# ADC-Peripherals.net
KiCad netlist of a schematic drawn in Altium Designer
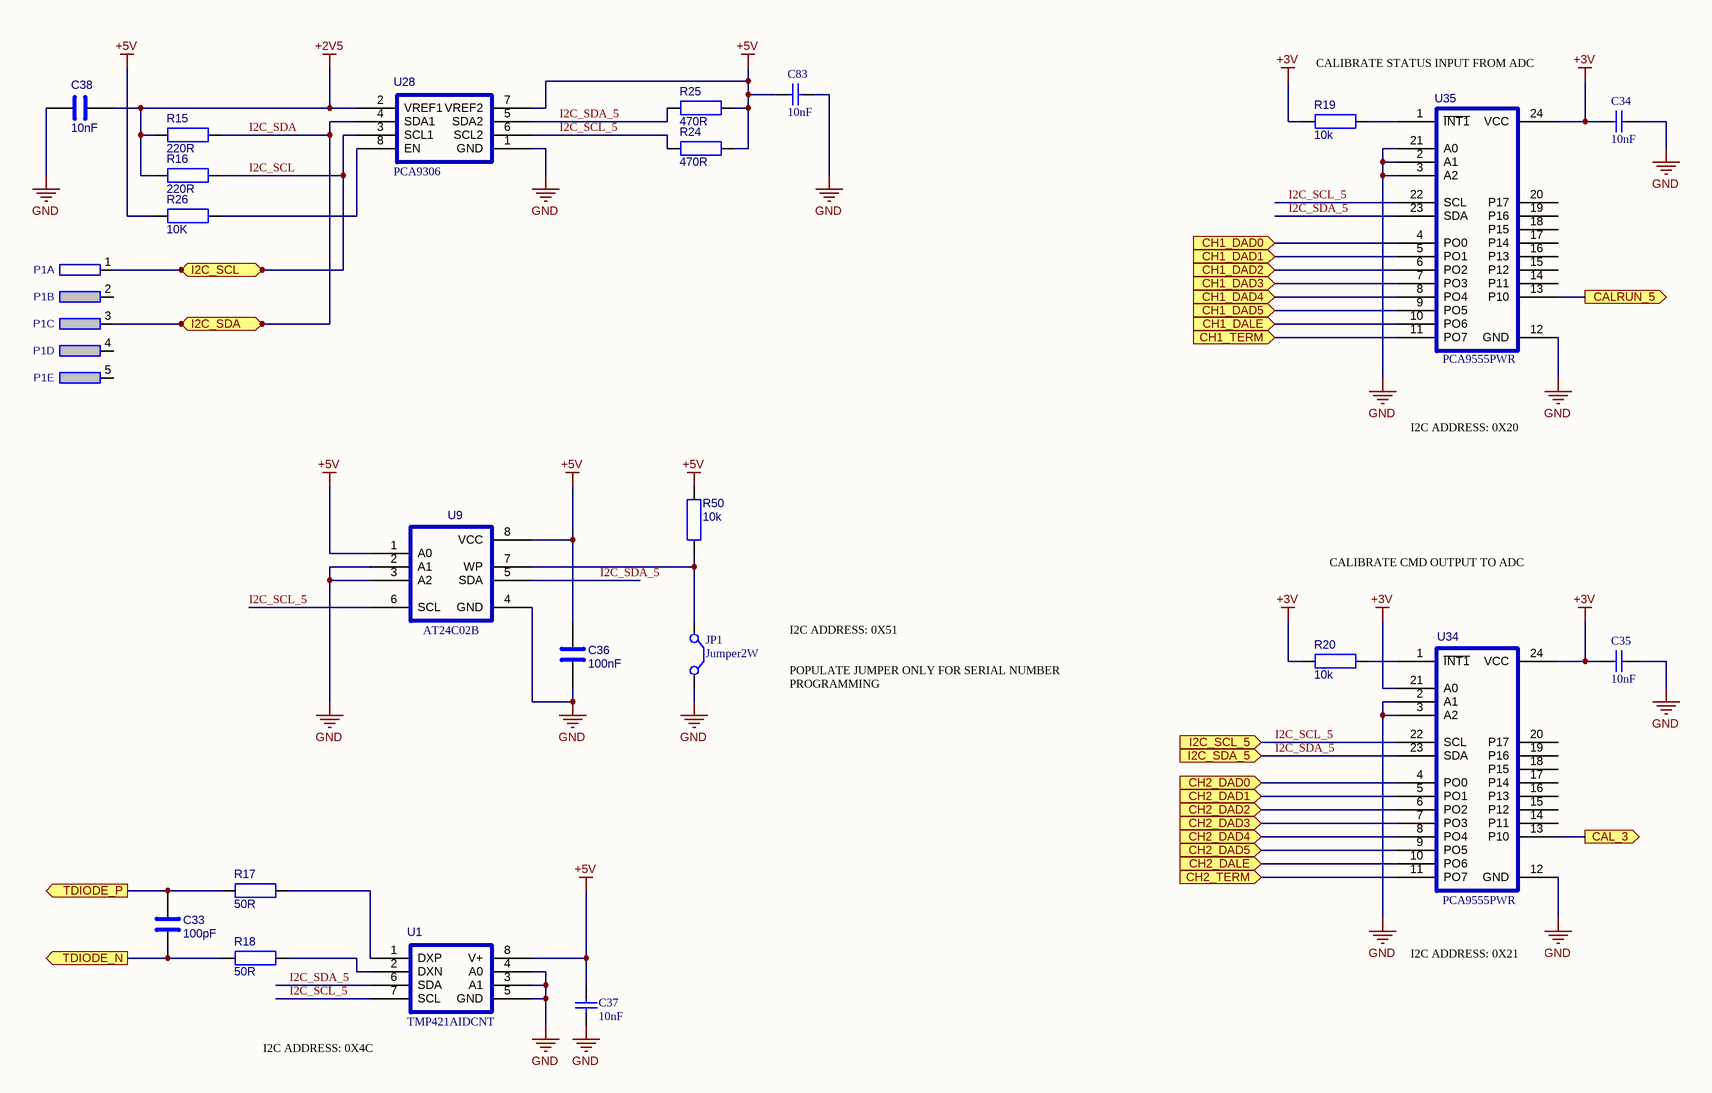
[diagram p0: ADC-Peripherals.SchDoc]

(export (version "E")
  (design (tool "Eeschema 10.0.6"))
  (components
    (comp (ref "C33")
      (value "100pF")
      (footprint "CAPC1005X55N")
      (description "CAP SMD 0603")
      (fields (field (name "CREATED_BY") "*") (field (name "CHECKED_BY") "*"))
      (libsource (lib "Abdus-TEMP") (part "CAP-0603"))
    )
    (comp (ref "C34")
      (value "10nF")
      (footprint "CAPC1005X55N")
      (description "Capacitor 0402 SMD")
      (fields (field (name "CREATED_BY") "EDA-ASA") (field (name "CHECKED_BY") "*"))
      (libsource (lib "EDA-Passive") (part "cap0402"))
    )
    (comp (ref "C35")
      (value "10nF")
      (footprint "CAPC1005X55N")
      (description "Capacitor 0402 SMD")
      (fields (field (name "CREATED_BY") "EDA-ASA") (field (name "CHECKED_BY") "*"))
      (libsource (lib "EDA-Passive") (part "cap0402"))
    )
    (comp (ref "C36")
      (value "100nF")
      (footprint "CAPC1005X55N")
      (description "CAP SMD 0603")
      (fields (field (name "CREATED_BY") "*") (field (name "CHECKED_BY") "*"))
      (libsource (lib "Abdus-TEMP") (part "CAP-0603"))
    )
    (comp (ref "C37")
      (value "10nF")
      (footprint "CAPC1005X55N")
      (description "Capacitor 0402 SMD")
      (fields (field (name "CREATED_BY") "EDA-ASA") (field (name "CHECKED_BY") "*"))
      (libsource (lib "EDA-Passive") (part "cap0402"))
    )
    (comp (ref "C38")
      (value "10nF")
      (footprint "CAPC1005X55N")
      (description "CAP SMD 0603")
      (fields (field (name "CREATED_BY") "*") (field (name "CHECKED_BY") "*"))
      (libsource (lib "Abdus-TEMP") (part "CAP-0603"))
    )
    (comp (ref "C83")
      (value "10nF")
      (footprint "CAPC1005X55N")
      (description "Capacitor 0402 SMD")
      (fields (field (name "CREATED_BY") "EDA-ASA") (field (name "CHECKED_BY") "*"))
      (libsource (lib "EDA-Passive") (part "cap0402"))
    )
    (comp (ref "JP1")
      (value "Jumper2W")
      (footprint "JP-100MIL")
      (description "Jumper Wire")
      (fields (field (name "PUBLISHER") "Altium Limited"))
      (libsource (lib "EDA-Hardware") (part "Jumper2W"))
    )
    (comp (ref "P1")
      (value "SAMTEC-TSM-105-01-TM-SV-5W-HDR")
      (footprint "TSM_5X1_SV")
      (libsource (lib "Ish") (part "SAMTEC-TSM-105-01-TM-SV-5W-HDR"))
    )
    (comp (ref "R15")
      (value "220R")
      (footprint "0603")
      (description "RESISTOR SMD 0805")
      (fields (field (name "CREATED_BY") "*") (field (name "CHECKED_BY") "NN"))
      (libsource (lib "EDA_Passive") (part "RES-0805"))
    )
    (comp (ref "R16")
      (value "220R")
      (footprint "0603")
      (description "RESISTOR SMD 0805")
      (fields (field (name "CREATED_BY") "*") (field (name "CHECKED_BY") "NN"))
      (libsource (lib "EDA_Passive") (part "RES-0805"))
    )
    (comp (ref "R17")
      (value "50R")
      (footprint "RESC1005X40N")
      (description "RESISTOR SMD 0805")
      (fields (field (name "CREATED_BY") "*") (field (name "CHECKED_BY") "NN"))
      (libsource (lib "EDA_Passive") (part "RES-0805"))
    )
    (comp (ref "R18")
      (value "50R")
      (footprint "RESC1005X40N")
      (description "RESISTOR SMD 0805")
      (fields (field (name "CREATED_BY") "*") (field (name "CHECKED_BY") "NN"))
      (libsource (lib "EDA_Passive") (part "RES-0805"))
    )
    (comp (ref "R19")
      (value "10k")
      (footprint "0603")
      (description "RESISTOR SMD 0805")
      (fields (field (name "CREATED_BY") "*") (field (name "CHECKED_BY") "NN"))
      (libsource (lib "EDA_Passive") (part "RES-0805"))
    )
    (comp (ref "R20")
      (value "10k")
      (footprint "0603")
      (description "RESISTOR SMD 0805")
      (fields (field (name "CREATED_BY") "*") (field (name "CHECKED_BY") "NN"))
      (libsource (lib "EDA_Passive") (part "RES-0805"))
    )
    (comp (ref "R24")
      (value "470R")
      (footprint "0603")
      (description "RESISTOR SMD 0805")
      (fields (field (name "CREATED_BY") "*") (field (name "CHECKED_BY") "NN"))
      (libsource (lib "EDA_Passive") (part "RES-0805"))
    )
    (comp (ref "R25")
      (value "470R")
      (footprint "0603")
      (description "RESISTOR SMD 0805")
      (fields (field (name "CREATED_BY") "*") (field (name "CHECKED_BY") "NN"))
      (libsource (lib "EDA_Passive") (part "RES-0805"))
    )
    (comp (ref "R26")
      (value "10K")
      (footprint "0603")
      (description "RESISTOR SMD 0805")
      (fields (field (name "CREATED_BY") "*") (field (name "CHECKED_BY") "NN"))
      (libsource (lib "EDA_Passive") (part "RES-0805"))
    )
    (comp (ref "R50")
      (value "10k")
      (footprint "0603")
      (description "RESISTOR SMD 0805")
      (fields (field (name "CREATED_BY") "*") (field (name "CHECKED_BY") "NN"))
      (libsource (lib "EDA_Passive") (part "RES-0805"))
    )
    (comp (ref "U1")
      (value "TMP421AIDCNT")
      (footprint "TI_SOT23-8")
      (description "Remote and Local TempreatureSensor in SOT23-8")
      (fields
        (field (name "MANUFACTURER") "TI")
        (field (name "CREATED_BY") "IN")
        (field (name "CHECKED_BY") "*")
      )
      (libsource (lib "Ishvah-TEMP") (part "TMP421AIDCNT"))
    )
    (comp (ref "U9")
      (value "AT24C02B")
      (footprint "SOIC127P600X175-8N")
      (description "Two wire Serial EEPROM 2K (256 x 8)")
      (fields
        (field (name "MANUFACTURER") "Atmel")
        (field (name "CREATED_BY") "IN")
        (field (name "CHECKED_BY") "*")
      )
      (libsource (lib "Ishvah-TEMP") (part "AT24C02B"))
    )
    (comp (ref "U28")
      (value "PCA9306")
      (footprint "SOP65P400X130-8USR")
      (description "Dual Bidirectional I2C Bus and SMBus Voltage-Level Translator")
      (fields
        (field (name "MANUFACTURER") "TI")
        (field (name "CREATED_BY") "IN")
        (field (name "CHECKED_BY") "*")
      )
      (libsource (lib "Ishvah-TEMP") (part "PCA9306DCTR"))
    )
    (comp (ref "U34")
      (value "PCA9555PWR")
      (footprint "TI_TSSOP24")
      (description "Remote 16-Bit I2C and SMBus  I/O expander")
      (fields
        (field (name "MANUFACTURER") "TI")
        (field (name "CREATED_BY") "IN")
        (field (name "CHECKED_BY") "*")
      )
      (libsource (lib "Ishvah-TEMP") (part "PCA9555PWR"))
    )
    (comp (ref "U35")
      (value "PCA9555PWR")
      (footprint "TI_TSSOP24")
      (description "Remote 16-Bit I2C and SMBus  I/O expander")
      (fields
        (field (name "MANUFACTURER") "TI")
        (field (name "CREATED_BY") "IN")
        (field (name "CHECKED_BY") "*")
      )
      (libsource (lib "Ishvah-TEMP") (part "PCA9555PWR"))
    )
  )
  (nets
    (net (code "1") (name "+2V5") (class "Default")
      (node (ref "C38") (pin "2") (pinfunction "2_2") (pintype "passive"))
      (node (ref "R15") (pin "1") (pinfunction "1_1") (pintype "passive"))
      (node (ref "R16") (pin "1") (pinfunction "1_1") (pintype "passive"))
      (node (ref "U28") (pin "2") (pinfunction "VREF1_2") (pintype "passive"))
    )
    (net (code "2") (name "+3V") (class "Default")
      (node (ref "C34") (pin "1") (pinfunction "1_1") (pintype "passive"))
      (node (ref "C35") (pin "1") (pinfunction "1_1") (pintype "passive"))
      (node (ref "R19") (pin "1") (pinfunction "1_1") (pintype "passive"))
      (node (ref "R20") (pin "1") (pinfunction "1_1") (pintype "passive"))
      (node (ref "U34") (pin "21") (pinfunction "A0_21") (pintype "passive"))
      (node (ref "U34") (pin "24") (pinfunction "VCC_24") (pintype "passive"))
      (node (ref "U35") (pin "24") (pinfunction "VCC_24") (pintype "passive"))
    )
    (net (code "3") (name "+5V") (class "Default")
      (node (ref "C36") (pin "1") (pinfunction "1_1") (pintype "passive"))
      (node (ref "C37") (pin "2") (pinfunction "2_2") (pintype "passive"))
      (node (ref "C83") (pin "1") (pinfunction "1_1") (pintype "passive"))
      (node (ref "R24") (pin "2") (pinfunction "2_2") (pintype "passive"))
      (node (ref "R25") (pin "2") (pinfunction "2_2") (pintype "passive"))
      (node (ref "R26") (pin "2") (pinfunction "2_2") (pintype "passive"))
      (node (ref "R50") (pin "1") (pinfunction "1_1") (pintype "passive"))
      (node (ref "U1") (pin "8") (pinfunction "V+_8") (pintype "passive"))
      (node (ref "U28") (pin "7") (pinfunction "VREF2_7") (pintype "passive"))
      (node (ref "U9") (pin "1") (pinfunction "A0_1") (pintype "passive"))
      (node (ref "U9") (pin "8") (pinfunction "VCC_8") (pintype "passive"))
    )
    (net (code "4") (name "/CALRUN_5") (class "Default")
      (node (ref "U35") (pin "13") (pinfunction "P10_13") (pintype "passive"))
    )
    (net (code "5") (name "/CAL_3") (class "Default")
      (node (ref "U34") (pin "13") (pinfunction "P10_13") (pintype "passive"))
    )
    (net (code "6") (name "/CH1_DAD0") (class "Default")
      (node (ref "U35") (pin "4") (pinfunction "PO0_4") (pintype "passive"))
    )
    (net (code "7") (name "/CH1_DAD1") (class "Default")
      (node (ref "U35") (pin "5") (pinfunction "PO1_5") (pintype "passive"))
    )
    (net (code "8") (name "/CH1_DAD2") (class "Default")
      (node (ref "U35") (pin "6") (pinfunction "PO2_6") (pintype "passive"))
    )
    (net (code "9") (name "/CH1_DAD3") (class "Default")
      (node (ref "U35") (pin "7") (pinfunction "PO3_7") (pintype "passive"))
    )
    (net (code "10") (name "/CH1_DAD4") (class "Default")
      (node (ref "U35") (pin "8") (pinfunction "PO4_8") (pintype "passive"))
    )
    (net (code "11") (name "/CH1_DAD5") (class "Default")
      (node (ref "U35") (pin "9") (pinfunction "PO5_9") (pintype "passive"))
    )
    (net (code "12") (name "/CH1_DALE") (class "Default")
      (node (ref "U35") (pin "10") (pinfunction "PO6_10") (pintype "passive"))
    )
    (net (code "13") (name "/CH1_TERM") (class "Default")
      (node (ref "U35") (pin "11") (pinfunction "PO7_11") (pintype "passive"))
    )
    (net (code "14") (name "/CH2_DAD0") (class "Default")
      (node (ref "U34") (pin "4") (pinfunction "PO0_4") (pintype "passive"))
    )
    (net (code "15") (name "/CH2_DAD1") (class "Default")
      (node (ref "U34") (pin "5") (pinfunction "PO1_5") (pintype "passive"))
    )
    (net (code "16") (name "/CH2_DAD2") (class "Default")
      (node (ref "U34") (pin "6") (pinfunction "PO2_6") (pintype "passive"))
    )
    (net (code "17") (name "/CH2_DAD3") (class "Default")
      (node (ref "U34") (pin "7") (pinfunction "PO3_7") (pintype "passive"))
    )
    (net (code "18") (name "/CH2_DAD4") (class "Default")
      (node (ref "U34") (pin "8") (pinfunction "PO4_8") (pintype "passive"))
    )
    (net (code "19") (name "/CH2_DAD5") (class "Default")
      (node (ref "U34") (pin "9") (pinfunction "PO5_9") (pintype "passive"))
    )
    (net (code "20") (name "/CH2_DALE") (class "Default")
      (node (ref "U34") (pin "10") (pinfunction "PO6_10") (pintype "passive"))
    )
    (net (code "21") (name "/CH2_TERM") (class "Default")
      (node (ref "U34") (pin "11") (pinfunction "PO7_11") (pintype "passive"))
    )
    (net (code "22") (name "/I2C_SCL") (class "Default")
      (node (ref "P1") (pin "1") (pintype "passive"))
      (node (ref "R16") (pin "2") (pinfunction "2_2") (pintype "passive"))
      (node (ref "U28") (pin "3") (pinfunction "SCL1_3") (pintype "passive"))
    )
    (net (code "23") (name "/I2C_SCL_5") (class "Default")
      (node (ref "R24") (pin "1") (pinfunction "1_1") (pintype "passive"))
      (node (ref "U1") (pin "7") (pinfunction "SCL_7") (pintype "passive"))
      (node (ref "U28") (pin "6") (pinfunction "SCL2_6") (pintype "passive"))
      (node (ref "U34") (pin "22") (pinfunction "SCL_22") (pintype "passive"))
      (node (ref "U35") (pin "22") (pinfunction "SCL_22") (pintype "passive"))
      (node (ref "U9") (pin "6") (pinfunction "SCL_6") (pintype "passive"))
    )
    (net (code "24") (name "/I2C_SDA") (class "Default")
      (node (ref "P1") (pin "3") (pintype "passive"))
      (node (ref "R15") (pin "2") (pinfunction "2_2") (pintype "passive"))
      (node (ref "U28") (pin "4") (pinfunction "SDA1_4") (pintype "passive"))
    )
    (net (code "25") (name "/I2C_SDA_5") (class "Default")
      (node (ref "R25") (pin "1") (pinfunction "1_1") (pintype "passive"))
      (node (ref "U1") (pin "6") (pinfunction "SDA_6") (pintype "passive"))
      (node (ref "U28") (pin "5") (pinfunction "SDA2_5") (pintype "passive"))
      (node (ref "U34") (pin "23") (pinfunction "SDA_23") (pintype "passive"))
      (node (ref "U35") (pin "23") (pinfunction "SDA_23") (pintype "passive"))
      (node (ref "U9") (pin "5") (pinfunction "SDA_5") (pintype "passive"))
    )
    (net (code "26") (name "/TDIODE_N") (class "Default")
      (node (ref "C33") (pin "2") (pinfunction "2_2") (pintype "passive"))
      (node (ref "R18") (pin "2") (pinfunction "2_2") (pintype "passive"))
    )
    (net (code "27") (name "/TDIODE_P") (class "Default")
      (node (ref "C33") (pin "1") (pinfunction "1_1") (pintype "passive"))
      (node (ref "R17") (pin "2") (pinfunction "2_2") (pintype "passive"))
    )
    (net (code "28") (name "GND") (class "Default")
      (node (ref "C34") (pin "2") (pinfunction "2_2") (pintype "passive"))
      (node (ref "C35") (pin "2") (pinfunction "2_2") (pintype "passive"))
      (node (ref "C36") (pin "2") (pinfunction "2_2") (pintype "passive"))
      (node (ref "C37") (pin "1") (pinfunction "1_1") (pintype "passive"))
      (node (ref "C38") (pin "1") (pinfunction "1_1") (pintype "passive"))
      (node (ref "C83") (pin "2") (pinfunction "2_2") (pintype "passive"))
      (node (ref "JP1") (pin "2") (pinfunction "C2_2") (pintype "passive"))
      (node (ref "U1") (pin "3") (pinfunction "A1_3") (pintype "passive"))
      (node (ref "U1") (pin "4") (pinfunction "A0_4") (pintype "passive"))
      (node (ref "U1") (pin "5") (pinfunction "GND_5") (pintype "passive"))
      (node (ref "U28") (pin "1") (pinfunction "GND_1") (pintype "passive"))
      (node (ref "U34") (pin "12") (pinfunction "GND_12") (pintype "passive"))
      (node (ref "U34") (pin "2") (pinfunction "A1_2") (pintype "passive"))
      (node (ref "U34") (pin "3") (pinfunction "A2_3") (pintype "passive"))
      (node (ref "U35") (pin "12") (pinfunction "GND_12") (pintype "passive"))
      (node (ref "U35") (pin "2") (pinfunction "A1_2") (pintype "passive"))
      (node (ref "U35") (pin "21") (pinfunction "A0_21") (pintype "passive"))
      (node (ref "U35") (pin "3") (pinfunction "A2_3") (pintype "passive"))
      (node (ref "U9") (pin "2") (pinfunction "A1_2") (pintype "passive"))
      (node (ref "U9") (pin "3") (pinfunction "A2_3") (pintype "passive"))
      (node (ref "U9") (pin "4") (pinfunction "GND_4") (pintype "power_in"))
    )
    (net (code "29") (name "Net-(JP1-C1)") (class "Default")
      (node (ref "JP1") (pin "1") (pinfunction "C1_1") (pintype "passive"))
      (node (ref "R50") (pin "2") (pinfunction "2_2") (pintype "passive"))
      (node (ref "U9") (pin "7") (pinfunction "WP_7") (pintype "passive"))
    )
    (net (code "30") (name "Net-(U1-DXN)") (class "Default")
      (node (ref "R18") (pin "1") (pinfunction "1_1") (pintype "passive"))
      (node (ref "U1") (pin "2") (pinfunction "DXN_2") (pintype "passive"))
    )
    (net (code "31") (name "Net-(U1-DXP)") (class "Default")
      (node (ref "R17") (pin "1") (pinfunction "1_1") (pintype "passive"))
      (node (ref "U1") (pin "1") (pinfunction "DXP_1") (pintype "passive"))
    )
    (net (code "32") (name "Net-(U28-EN)") (class "Default")
      (node (ref "R26") (pin "1") (pinfunction "1_1") (pintype "passive"))
      (node (ref "U28") (pin "8") (pinfunction "EN_8") (pintype "passive"))
    )
    (net (code "33") (name "Net-(U34-INT1)") (class "Default")
      (node (ref "R20") (pin "2") (pinfunction "2_2") (pintype "passive"))
      (node (ref "U34") (pin "1") (pinfunction "INT1_1") (pintype "passive"))
    )
    (net (code "34") (name "Net-(U35-INT1)") (class "Default")
      (node (ref "R19") (pin "2") (pinfunction "2_2") (pintype "passive"))
      (node (ref "U35") (pin "1") (pinfunction "INT1_1") (pintype "passive"))
    )
    (net (code "35") (name "unconnected-(P1-Pad2)") (class "Default")
      (node (ref "P1") (pin "2") (pintype "passive"))
    )
    (net (code "36") (name "unconnected-(P1-Pad4)") (class "Default")
      (node (ref "P1") (pin "4") (pintype "passive"))
    )
    (net (code "37") (name "unconnected-(P1-Pad5)") (class "Default")
      (node (ref "P1") (pin "5") (pintype "passive"))
    )
    (net (code "38") (name "unconnected-(U34-P11-Pad14)") (class "Default")
      (node (ref "U34") (pin "14") (pinfunction "P11_14") (pintype "passive"))
    )
    (net (code "39") (name "unconnected-(U34-P12-Pad15)") (class "Default")
      (node (ref "U34") (pin "15") (pinfunction "P12_15") (pintype "passive"))
    )
    (net (code "40") (name "unconnected-(U34-P13-Pad16)") (class "Default")
      (node (ref "U34") (pin "16") (pinfunction "P13_16") (pintype "passive"))
    )
    (net (code "41") (name "unconnected-(U34-P14-Pad17)") (class "Default")
      (node (ref "U34") (pin "17") (pinfunction "P14_17") (pintype "passive"))
    )
    (net (code "42") (name "unconnected-(U34-P15-Pad18)") (class "Default")
      (node (ref "U34") (pin "18") (pinfunction "P15_18") (pintype "passive"))
    )
    (net (code "43") (name "unconnected-(U34-P16-Pad19)") (class "Default")
      (node (ref "U34") (pin "19") (pinfunction "P16_19") (pintype "passive"))
    )
    (net (code "44") (name "unconnected-(U34-P17-Pad20)") (class "Default")
      (node (ref "U34") (pin "20") (pinfunction "P17_20") (pintype "passive"))
    )
    (net (code "45") (name "unconnected-(U35-P11-Pad14)") (class "Default")
      (node (ref "U35") (pin "14") (pinfunction "P11_14") (pintype "passive"))
    )
    (net (code "46") (name "unconnected-(U35-P12-Pad15)") (class "Default")
      (node (ref "U35") (pin "15") (pinfunction "P12_15") (pintype "passive"))
    )
    (net (code "47") (name "unconnected-(U35-P13-Pad16)") (class "Default")
      (node (ref "U35") (pin "16") (pinfunction "P13_16") (pintype "passive"))
    )
    (net (code "48") (name "unconnected-(U35-P14-Pad17)") (class "Default")
      (node (ref "U35") (pin "17") (pinfunction "P14_17") (pintype "passive"))
    )
    (net (code "49") (name "unconnected-(U35-P15-Pad18)") (class "Default")
      (node (ref "U35") (pin "18") (pinfunction "P15_18") (pintype "passive"))
    )
    (net (code "50") (name "unconnected-(U35-P16-Pad19)") (class "Default")
      (node (ref "U35") (pin "19") (pinfunction "P16_19") (pintype "passive"))
    )
    (net (code "51") (name "unconnected-(U35-P17-Pad20)") (class "Default")
      (node (ref "U35") (pin "20") (pinfunction "P17_20") (pintype "passive"))
    )
  )
)
